# 5V_buck.net
KiCad netlist of a schematic drawn in Altium Designer
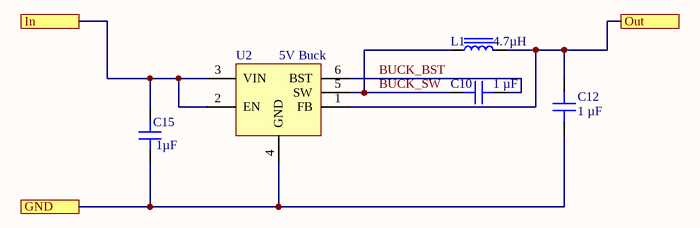
[diagram p0: 5V_buck.SchDoc]

(export (version "E")
  (design (tool "Eeschema 10.0.6"))
  (components
    (comp (ref "C10")
      (value "1 µF")
      (footprint "CAP 0402_1005")
      (description "CAP CER 0.1UF 16V X7R 0402")
      (fields (field (name "PART NUMBER") "C0402C104K4RACAUTO") (field (name "MANUFACTURER") "KEMET"))
      (libsource (lib "Celestial Altium Library - altium_library") (part "Capacitor"))
    )
    (comp (ref "C12")
      (value "1 µF")
      (footprint "CAP 0402_1005")
      (description "CAP CER 0.1UF 16V X7R 0402")
      (fields (field (name "PART NUMBER") "C0402C104K4RACAUTO") (field (name "MANUFACTURER") "KEMET"))
      (libsource (lib "Celestial Altium Library - altium_library") (part "Capacitor"))
    )
    (comp (ref "C15")
      (value "1µF")
      (footprint "CAP 0603_1608")
      (description "CAP CER 0.1UF 100V 0603 EPOXY")
      (fields
        (field (name "PART NUMBER") "GCG188R92A104KA03D")
        (field (name "MANUFACTURER") "Murata Electronics")
      )
      (libsource (lib "Celestial Altium Library - altium_library") (part "Capacitor"))
    )
    (comp (ref "L1")
      (value "4.7µH")
      (footprint "IND 1008_2520")
      (description "FIXED IND 4.7UH 1A 110 MOHM SMD")
      (fields (field (name "PART NUMBER") "MLP2520S4R7ST0S1") (field (name "MANUFACTURER") "TDK Corporation"))
      (libsource (lib "Celestial Altium Library - altium_library") (part "Inductor"))
    )
    (comp (ref "U2")
      (value "5V Buck")
      (footprint "TSOT-26-6 - 3.2mm")
      (description "5V fixed step down Buck")
      (libsource (lib "IC") (part "AP63205WU-7"))
    )
  )
  (nets
    (net (code "1") (name "/BUCK_BST") (class "Default")
      (node (ref "C10") (pin "2") (pinfunction "2_2") (pintype "passive"))
      (node (ref "U2") (pin "6") (pinfunction "BST_6") (pintype "passive"))
    )
    (net (code "2") (name "/BUCK_SW") (class "Default")
      (node (ref "C10") (pin "1") (pinfunction "1_1") (pintype "passive"))
      (node (ref "L1") (pin "1") (pinfunction "1_1") (pintype "passive"))
      (node (ref "U2") (pin "5") (pinfunction "SW_5") (pintype "passive"))
    )
    (net (code "3") (name "/GND") (class "Default")
      (node (ref "C12") (pin "1") (pinfunction "1_1") (pintype "passive"))
      (node (ref "C15") (pin "2") (pinfunction "2_2") (pintype "passive"))
      (node (ref "U2") (pin "4") (pinfunction "GND_4") (pintype "passive"))
    )
    (net (code "4") (name "/In") (class "Default")
      (node (ref "C15") (pin "1") (pinfunction "1_1") (pintype "passive"))
      (node (ref "U2") (pin "2") (pinfunction "EN_2") (pintype "passive"))
      (node (ref "U2") (pin "3") (pinfunction "VIN_3") (pintype "passive"))
    )
    (net (code "5") (name "/Out") (class "Default")
      (node (ref "C12") (pin "2") (pinfunction "2_2") (pintype "passive"))
      (node (ref "L1") (pin "2") (pinfunction "2_2") (pintype "passive"))
      (node (ref "U2") (pin "1") (pinfunction "FB_1") (pintype "passive"))
    )
  )
)
